# processor_board.net
KiCad netlist of a schematic drawn in EAGLE
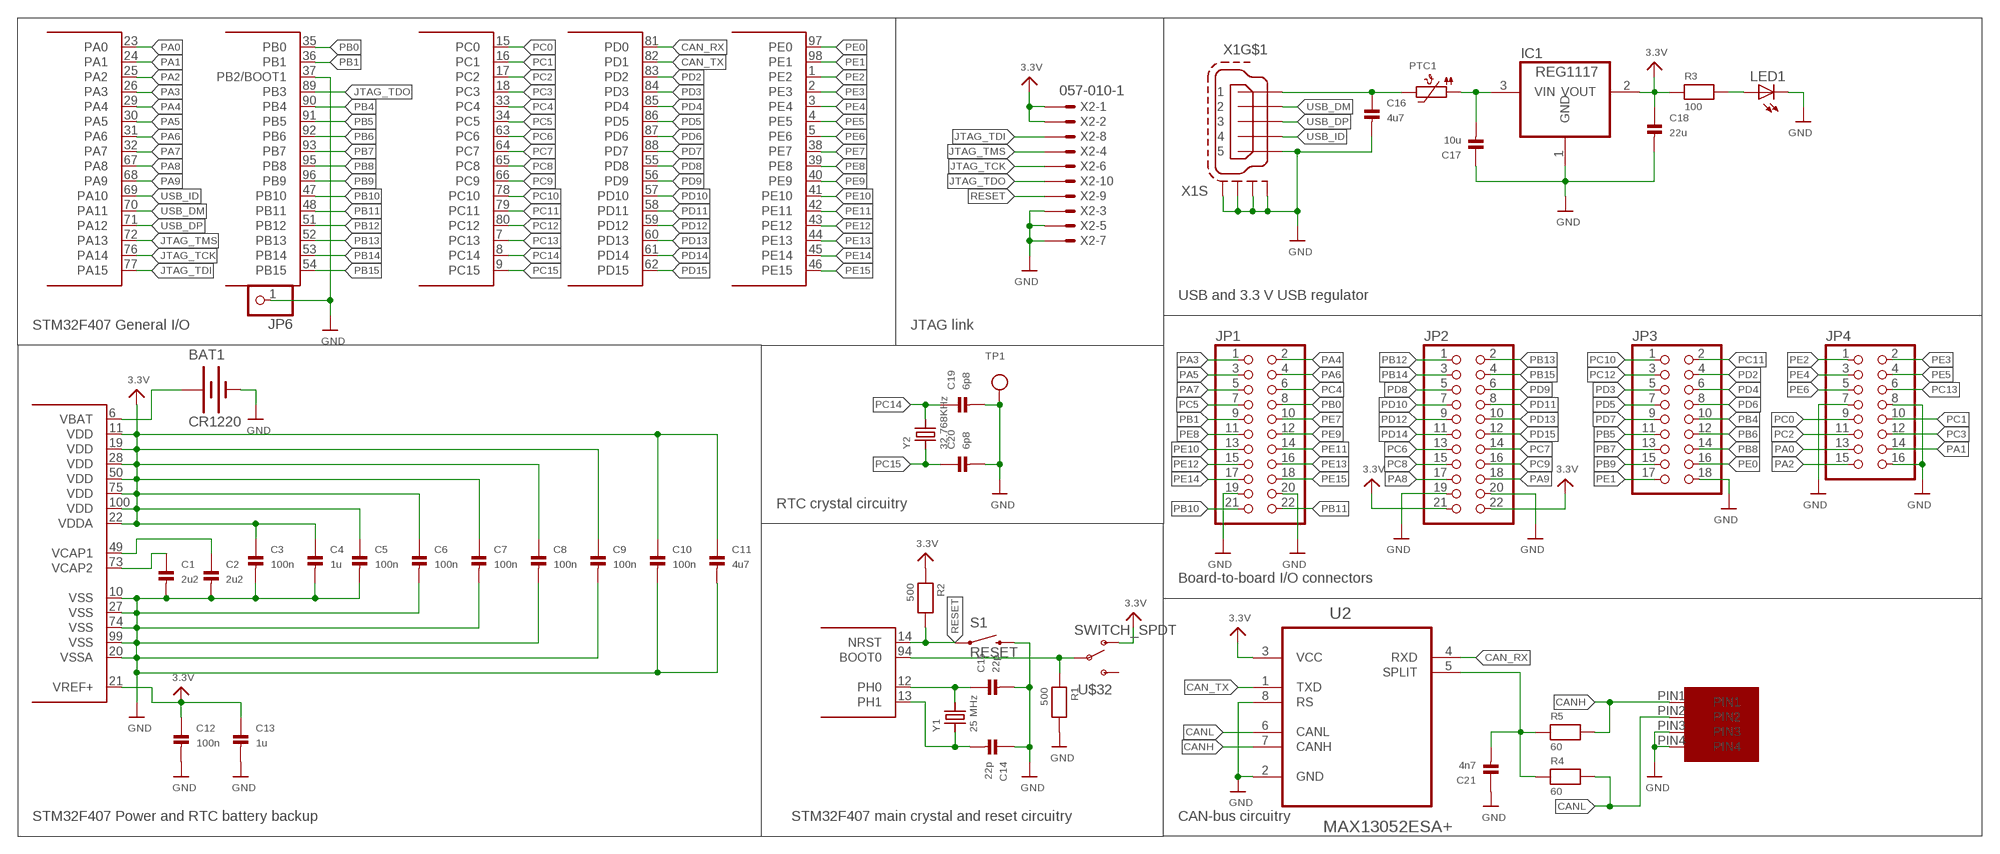
[diagram p0: schematic, sheet 1]

(export (version "E")
  (design (tool "Eeschema 10.0.6"))
  (components
    (comp (ref "BAT1")
      (value "CR1220")
      (footprint "eagle-import:BATTCON_12MM_PTH")
      (libsource (lib "eagle-import") (part "BATTERY12PTH"))
    )
    (comp (ref "C1")
      (value "2u2")
      (footprint "eagle-import:_0603MP")
      (libsource (lib "eagle-import") (part "CAP_CERAMIC_0603MP"))
    )
    (comp (ref "C2")
      (value "2u2")
      (footprint "eagle-import:_0603MP")
      (libsource (lib "eagle-import") (part "CAP_CERAMIC_0603MP"))
    )
    (comp (ref "C3")
      (value "100n")
      (footprint "eagle-import:_0603MP")
      (libsource (lib "eagle-import") (part "CAP_CERAMIC_0603MP"))
    )
    (comp (ref "C4")
      (value "1u")
      (footprint "eagle-import:_0603MP")
      (libsource (lib "eagle-import") (part "CAP_CERAMIC_0603MP"))
    )
    (comp (ref "C5")
      (value "100n")
      (footprint "eagle-import:_0603MP")
      (libsource (lib "eagle-import") (part "CAP_CERAMIC_0603MP"))
    )
    (comp (ref "C6")
      (value "100n")
      (footprint "eagle-import:_0603MP")
      (libsource (lib "eagle-import") (part "CAP_CERAMIC_0603MP"))
    )
    (comp (ref "C7")
      (value "100n")
      (footprint "eagle-import:_0603MP")
      (libsource (lib "eagle-import") (part "CAP_CERAMIC_0603MP"))
    )
    (comp (ref "C8")
      (value "100n")
      (footprint "eagle-import:_0603MP")
      (libsource (lib "eagle-import") (part "CAP_CERAMIC_0603MP"))
    )
    (comp (ref "C9")
      (value "100n")
      (footprint "eagle-import:_0603MP")
      (libsource (lib "eagle-import") (part "CAP_CERAMIC_0603MP"))
    )
    (comp (ref "C10")
      (value "100n")
      (footprint "eagle-import:_0603MP")
      (libsource (lib "eagle-import") (part "CAP_CERAMIC_0603MP"))
    )
    (comp (ref "C11")
      (value "4u7")
      (footprint "eagle-import:_0603MP")
      (libsource (lib "eagle-import") (part "CAP_CERAMIC_0603MP"))
    )
    (comp (ref "C12")
      (value "100n")
      (footprint "eagle-import:_0603MP")
      (libsource (lib "eagle-import") (part "CAP_CERAMIC_0603MP"))
    )
    (comp (ref "C13")
      (value "1u")
      (footprint "eagle-import:_0603MP")
      (libsource (lib "eagle-import") (part "CAP_CERAMIC_0603MP"))
    )
    (comp (ref "C14")
      (value "22p")
      (footprint "eagle-import:_0603MP")
      (libsource (lib "eagle-import") (part "CAP_CERAMIC_0603MP"))
    )
    (comp (ref "C15")
      (value "22p")
      (footprint "eagle-import:_0603MP")
      (libsource (lib "eagle-import") (part "CAP_CERAMIC_0603MP"))
    )
    (comp (ref "C16")
      (value "4u7")
      (footprint "eagle-import:_0603MP")
      (libsource (lib "eagle-import") (part "CAP_CERAMIC_0603MP"))
    )
    (comp (ref "C17")
      (value "10u")
      (footprint "eagle-import:_0603MP")
      (libsource (lib "eagle-import") (part "CAP_CERAMIC_0603MP"))
    )
    (comp (ref "C18")
      (value "22u")
      (footprint "eagle-import:_0603MP")
      (libsource (lib "eagle-import") (part "CAP_CERAMIC_0603MP"))
    )
    (comp (ref "C19")
      (value "6p8")
      (footprint "eagle-import:_0603MP")
      (libsource (lib "eagle-import") (part "CAP_CERAMIC_0603MP"))
    )
    (comp (ref "C20")
      (value "6p8")
      (footprint "eagle-import:_0603MP")
      (libsource (lib "eagle-import") (part "CAP_CERAMIC_0603MP"))
    )
    (comp (ref "C21")
      (value "4n7")
      (footprint "eagle-import:_0603")
      (libsource (lib "eagle-import") (part "CAP_CERAMIC_0603"))
    )
    (comp (ref "IC1")
      (value "REG1117")
      (footprint "eagle-import:SOT223")
      (libsource (lib "eagle-import") (part "REG1117"))
    )
    (comp (ref "JP1")
      (value "PINHD-2X11")
      (footprint "eagle-import:2X11")
      (libsource (lib "eagle-import") (part "PINHD-2X11"))
    )
    (comp (ref "JP2")
      (value "PINHD-2X11")
      (footprint "eagle-import:2X11")
      (libsource (lib "eagle-import") (part "PINHD-2X11"))
    )
    (comp (ref "JP3")
      (value "PINHD-2X9")
      (footprint "eagle-import:2X09")
      (libsource (lib "eagle-import") (part "PINHD-2X9"))
    )
    (comp (ref "JP4")
      (value "PINHD-2X8")
      (footprint "eagle-import:2X08")
      (libsource (lib "eagle-import") (part "PINHD-2X8"))
    )
    (comp (ref "JP6")
      (value "PINHD-1X1")
      (footprint "eagle-import:1X01")
      (libsource (lib "eagle-import") (part "PINHD-1X1"))
    )
    (comp (ref "LED1")
      (value "LEDCHIPLED_1206")
      (footprint "eagle-import:CHIPLED_1206")
      (libsource (lib "eagle-import") (part "LEDCHIPLED_1206"))
    )
    (comp (ref "PTC1")
      (value "PTC1206")
      (footprint "eagle-import:1206")
      (libsource (lib "eagle-import") (part "PTC1206"))
    )
    (comp (ref "R1")
      (value "500")
      (footprint "eagle-import:_0603MP")
      (libsource (lib "eagle-import") (part "RESISTOR_0603MP"))
    )
    (comp (ref "R2")
      (value "500")
      (footprint "eagle-import:_0603MP")
      (libsource (lib "eagle-import") (part "RESISTOR_0603MP"))
    )
    (comp (ref "R3")
      (value "100")
      (footprint "eagle-import:_0603MP")
      (libsource (lib "eagle-import") (part "RESISTOR_0603MP"))
    )
    (comp (ref "R4")
      (value "60")
      (footprint "eagle-import:_0603")
      (libsource (lib "eagle-import") (part "RESISTOR_0603"))
    )
    (comp (ref "R5")
      (value "60")
      (footprint "eagle-import:_0603")
      (libsource (lib "eagle-import") (part "RESISTOR_0603"))
    )
    (comp (ref "S1")
      (value "RESET")
      (footprint "eagle-import:TACTILE-SWITCH-1101NE")
      (libsource (lib "eagle-import") (part "SWITCH-MOMENTARY-2SMD-1101NE"))
    )
    (comp (ref "TP1")
      (value "TESTPOINT0.1\"")
      (footprint "eagle-import:1X01_ROUND")
      (libsource (lib "eagle-import") (part "TESTPOINT0.1{dblquote}"))
    )
    (comp (ref "U$23")
      (value "MICROFIT4")
      (footprint "eagle-import:MICROFIT4SOCK")
      (libsource (lib "eagle-import") (part "MICROFIT4"))
    )
    (comp (ref "U$32")
      (value "SWITCH_SPDT")
      (footprint "eagle-import:KPS-1290")
      (libsource (lib "eagle-import") (part "SWITCH_SPDT"))
    )
    (comp (ref "U1")
      (value "STM32F4-100")
      (footprint "eagle-import:SQFP-S-14X14-100")
      (libsource (lib "eagle-import") (part "STM32F4-100"))
    )
    (comp (ref "U2")
      (value "MAX13052ESA+")
      (footprint "eagle-import:SOIC127P600X175-8N")
      (libsource (lib "eagle-import") (part "MAX13052ESA+"))
    )
    (comp (ref "X1")
      (value "MINI-USB-SCHIELD-32005-201")
      (footprint "eagle-import:32005-201")
      (libsource (lib "eagle-import") (part "MINI-USB-SCHIELD-32005-201"))
    )
    (comp (ref "X2")
      (value "057-010-1")
      (footprint "eagle-import:057-010-1")
      (libsource (lib "eagle-import") (part "057-010-1"))
    )
    (comp (ref "Y1")
      (value "25 MHz")
      (footprint "eagle-import:CRYSTAL_2.5X2")
      (libsource (lib "eagle-import") (part "CRYSTAL2.5X2.0MM"))
    )
    (comp (ref "Y2")
      (value "32.768KHz")
      (footprint "eagle-import:CRYSTAL_CYL_2X6MM_SMT")
      (libsource (lib "eagle-import") (part "CRYSTAL32.768"))
    )
  )
  (nets
    (net (code "1") (name "3.3V") (class "Default")
      (node (ref "C10") (pin "1") (pinfunction "P$1_1") (pintype "passive"))
      (node (ref "C11") (pin "1") (pinfunction "P$1_1") (pintype "passive"))
      (node (ref "C12") (pin "1") (pinfunction "P$1_1") (pintype "passive"))
      (node (ref "C13") (pin "1") (pinfunction "P$1_1") (pintype "passive"))
      (node (ref "C18") (pin "1") (pinfunction "P$1_1") (pintype "passive"))
      (node (ref "C3") (pin "1") (pinfunction "P$1_1") (pintype "passive"))
      (node (ref "C4") (pin "1") (pinfunction "P$1_1") (pintype "passive"))
      (node (ref "C5") (pin "1") (pinfunction "P$1_1") (pintype "passive"))
      (node (ref "C6") (pin "1") (pinfunction "P$1_1") (pintype "passive"))
      (node (ref "C7") (pin "1") (pinfunction "P$1_1") (pintype "passive"))
      (node (ref "C8") (pin "1") (pinfunction "P$1_1") (pintype "passive"))
      (node (ref "C9") (pin "1") (pinfunction "P$1_1") (pintype "passive"))
      (node (ref "IC1") (pin "2") (pinfunction "VOUT_2") (pintype "output"))
      (node (ref "JP2") (pin "21") (pinfunction "21_21") (pintype "passive"))
      (node (ref "JP2") (pin "22") (pinfunction "22_22") (pintype "passive"))
      (node (ref "R2") (pin "1") (pinfunction "1_1") (pintype "passive"))
      (node (ref "R3") (pin "1") (pinfunction "1_1") (pintype "passive"))
      (node (ref "U$32") (pin "O") (pinfunction "O_O") (pintype "passive"))
      (node (ref "U1") (pin "100") (pinfunction "VDD_100") (pintype "power_in"))
      (node (ref "U1") (pin "11") (pinfunction "VDD_11") (pintype "power_in"))
      (node (ref "U1") (pin "19") (pinfunction "VDD_19") (pintype "power_in"))
      (node (ref "U1") (pin "21") (pinfunction "VREF+_21") (pintype "passive"))
      (node (ref "U1") (pin "22") (pinfunction "VDDA_22") (pintype "power_in"))
      (node (ref "U1") (pin "28") (pinfunction "VDD_28") (pintype "power_in"))
      (node (ref "U1") (pin "50") (pinfunction "VDD_50") (pintype "power_in"))
      (node (ref "U1") (pin "75") (pinfunction "VDD_75") (pintype "power_in"))
      (node (ref "U2") (pin "3") (pinfunction "VCC_3") (pintype "power_in"))
      (node (ref "X2") (pin "1") (pinfunction "S_1") (pintype "passive"))
      (node (ref "X2") (pin "2") (pinfunction "S_2") (pintype "passive"))
    )
    (net (code "2") (name "CANH") (class "Default")
      (node (ref "R5") (pin "2") (pinfunction "2_2") (pintype "passive"))
      (node (ref "U$23") (pin "PIN1") (pinfunction "PIN1_PIN1") (pintype "bidirectional"))
      (node (ref "U2") (pin "7") (pinfunction "CANH_7") (pintype "input"))
    )
    (net (code "3") (name "CANL") (class "Default")
      (node (ref "R4") (pin "2") (pinfunction "2_2") (pintype "passive"))
      (node (ref "U$23") (pin "PIN2") (pinfunction "PIN2_PIN2") (pintype "bidirectional"))
      (node (ref "U2") (pin "6") (pinfunction "CANL_6") (pintype "input"))
    )
    (net (code "4") (name "CAN_RX") (class "Default")
      (node (ref "U1") (pin "81") (pinfunction "PD0_81") (pintype "bidirectional"))
      (node (ref "U2") (pin "4") (pinfunction "RXD_4") (pintype "output"))
    )
    (net (code "5") (name "CAN_TX") (class "Default")
      (node (ref "U1") (pin "82") (pinfunction "PD1_82") (pintype "bidirectional"))
      (node (ref "U2") (pin "1") (pinfunction "TXD_1") (pintype "input"))
    )
    (net (code "6") (name "GND") (class "Default")
      (node (ref "BAT1") (pin "GND") (pinfunction "-_GND") (pintype "power_in"))
      (node (ref "C1") (pin "2") (pinfunction "P$2_2") (pintype "passive"))
      (node (ref "C10") (pin "2") (pinfunction "P$2_2") (pintype "passive"))
      (node (ref "C11") (pin "2") (pinfunction "P$2_2") (pintype "passive"))
      (node (ref "C12") (pin "2") (pinfunction "P$2_2") (pintype "passive"))
      (node (ref "C13") (pin "2") (pinfunction "P$2_2") (pintype "passive"))
      (node (ref "C14") (pin "1") (pinfunction "P$1_1") (pintype "passive"))
      (node (ref "C15") (pin "2") (pinfunction "P$2_2") (pintype "passive"))
      (node (ref "C16") (pin "2") (pinfunction "P$2_2") (pintype "passive"))
      (node (ref "C17") (pin "1") (pinfunction "P$1_1") (pintype "passive"))
      (node (ref "C18") (pin "2") (pinfunction "P$2_2") (pintype "passive"))
      (node (ref "C19") (pin "2") (pinfunction "P$2_2") (pintype "passive"))
      (node (ref "C2") (pin "2") (pinfunction "P$2_2") (pintype "passive"))
      (node (ref "C20") (pin "2") (pinfunction "P$2_2") (pintype "passive"))
      (node (ref "C21") (pin "1") (pinfunction "P$1_1") (pintype "passive"))
      (node (ref "C3") (pin "2") (pinfunction "P$2_2") (pintype "passive"))
      (node (ref "C4") (pin "2") (pinfunction "P$2_2") (pintype "passive"))
      (node (ref "C5") (pin "2") (pinfunction "P$2_2") (pintype "passive"))
      (node (ref "C6") (pin "2") (pinfunction "P$2_2") (pintype "passive"))
      (node (ref "C7") (pin "2") (pinfunction "P$2_2") (pintype "passive"))
      (node (ref "C8") (pin "2") (pinfunction "P$2_2") (pintype "passive"))
      (node (ref "C9") (pin "2") (pinfunction "P$2_2") (pintype "passive"))
      (node (ref "IC1") (pin "1") (pinfunction "GND_1") (pintype "power_in"))
      (node (ref "JP1") (pin "19") (pinfunction "19_19") (pintype "passive"))
      (node (ref "JP1") (pin "20") (pinfunction "20_20") (pintype "passive"))
      (node (ref "JP2") (pin "19") (pinfunction "19_19") (pintype "passive"))
      (node (ref "JP2") (pin "20") (pinfunction "20_20") (pintype "passive"))
      (node (ref "JP3") (pin "18") (pinfunction "18_18") (pintype "passive"))
      (node (ref "JP4") (pin "16") (pinfunction "16_16") (pintype "passive"))
      (node (ref "JP4") (pin "7") (pinfunction "7_7") (pintype "passive"))
      (node (ref "JP4") (pin "8") (pinfunction "8_8") (pintype "passive"))
      (node (ref "JP6") (pin "1") (pinfunction "1_1") (pintype "passive"))
      (node (ref "LED1") (pin "C") (pinfunction "C_C") (pintype "passive"))
      (node (ref "R1") (pin "2") (pinfunction "2_2") (pintype "passive"))
      (node (ref "S1") (pin "2") (pinfunction "2_2") (pintype "passive"))
      (node (ref "TP1") (pin "1") (pinfunction "P$1_1") (pintype "bidirectional"))
      (node (ref "U$23") (pin "PIN3") (pinfunction "PIN3_PIN3") (pintype "bidirectional"))
      (node (ref "U$23") (pin "PIN4") (pinfunction "PIN4_PIN4") (pintype "bidirectional"))
      (node (ref "U1") (pin "10") (pinfunction "VSS_10") (pintype "power_in"))
      (node (ref "U1") (pin "20") (pinfunction "VSSA_20") (pintype "power_in"))
      (node (ref "U1") (pin "27") (pinfunction "VSS_27") (pintype "power_in"))
      (node (ref "U1") (pin "37") (pinfunction "PB2/BOOT1_37") (pintype "bidirectional"))
      (node (ref "U1") (pin "74") (pinfunction "VSS_74") (pintype "power_in"))
      (node (ref "U1") (pin "99") (pinfunction "VSS_99") (pintype "power_in"))
      (node (ref "U2") (pin "2") (pinfunction "GND_2") (pintype "passive"))
      (node (ref "U2") (pin "8") (pinfunction "RS_8") (pintype "input"))
      (node (ref "X1") (pin "5") (pinfunction "5_5") (pintype "passive"))
      (node (ref "X1") (pin "M1") (pinfunction "S1_M1") (pintype "passive"))
      (node (ref "X1") (pin "M2") (pinfunction "S2_M2") (pintype "passive"))
      (node (ref "X1") (pin "M3") (pinfunction "S3_M3") (pintype "passive"))
      (node (ref "X1") (pin "M4") (pinfunction "S4_M4") (pintype "passive"))
      (node (ref "X2") (pin "3") (pinfunction "S_3") (pintype "passive"))
      (node (ref "X2") (pin "5") (pinfunction "S_5") (pintype "passive"))
      (node (ref "X2") (pin "7") (pinfunction "S_7") (pintype "passive"))
    )
    (net (code "7") (name "JTAG_TCK") (class "Default")
      (node (ref "U1") (pin "76") (pinfunction "PA14_76") (pintype "bidirectional"))
      (node (ref "X2") (pin "6") (pinfunction "S_6") (pintype "passive"))
    )
    (net (code "8") (name "JTAG_TDI") (class "Default")
      (node (ref "U1") (pin "77") (pinfunction "PA15_77") (pintype "bidirectional"))
      (node (ref "X2") (pin "8") (pinfunction "S_8") (pintype "passive"))
    )
    (net (code "9") (name "JTAG_TDO") (class "Default")
      (node (ref "U1") (pin "89") (pinfunction "PB3_89") (pintype "bidirectional"))
      (node (ref "X2") (pin "10") (pinfunction "S_10") (pintype "passive"))
    )
    (net (code "10") (name "JTAG_TMS") (class "Default")
      (node (ref "U1") (pin "72") (pinfunction "PA13_72") (pintype "bidirectional"))
      (node (ref "X2") (pin "4") (pinfunction "S_4") (pintype "passive"))
    )
    (net (code "11") (name "Net-(BAT1-+)") (class "Default")
      (node (ref "BAT1") (pin "VCC@1") (pinfunction "+_VCC@1") (pintype "power_in"))
      (node (ref "U1") (pin "6") (pinfunction "VBAT_6") (pintype "power_in"))
    )
    (net (code "12") (name "Net-(C1-P$1)") (class "Default")
      (node (ref "C1") (pin "1") (pinfunction "P$1_1") (pintype "passive"))
      (node (ref "U1") (pin "73") (pinfunction "VCAP2_73") (pintype "passive"))
    )
    (net (code "13") (name "Net-(C2-P$1)") (class "Default")
      (node (ref "C2") (pin "1") (pinfunction "P$1_1") (pintype "passive"))
      (node (ref "U1") (pin "49") (pinfunction "VCAP1_49") (pintype "passive"))
    )
    (net (code "14") (name "Net-(C14-P$2)") (class "Default")
      (node (ref "C14") (pin "2") (pinfunction "P$2_2") (pintype "passive"))
      (node (ref "U1") (pin "13") (pinfunction "PH1_13") (pintype "bidirectional"))
      (node (ref "Y1") (pin "1") (pinfunction "1_1") (pintype "passive"))
    )
    (net (code "15") (name "Net-(C15-P$1)") (class "Default")
      (node (ref "C15") (pin "1") (pinfunction "P$1_1") (pintype "passive"))
      (node (ref "U1") (pin "12") (pinfunction "PH0_12") (pintype "bidirectional"))
      (node (ref "Y1") (pin "3") (pinfunction "2_3") (pintype "passive"))
    )
    (net (code "16") (name "Net-(C16-P$1)") (class "Default")
      (node (ref "C16") (pin "1") (pinfunction "P$1_1") (pintype "passive"))
      (node (ref "PTC1") (pin "2") (pinfunction "2_2") (pintype "passive"))
      (node (ref "X1") (pin "1") (pinfunction "1_1") (pintype "passive"))
    )
    (net (code "17") (name "Net-(C17-P$2)") (class "Default")
      (node (ref "C17") (pin "2") (pinfunction "P$2_2") (pintype "passive"))
      (node (ref "IC1") (pin "3") (pinfunction "VIN_3") (pintype "input"))
      (node (ref "PTC1") (pin "1") (pinfunction "1_1") (pintype "passive"))
    )
    (net (code "18") (name "Net-(C21-P$2)") (class "Default")
      (node (ref "C21") (pin "2") (pinfunction "P$2_2") (pintype "passive"))
      (node (ref "R4") (pin "1") (pinfunction "1_1") (pintype "passive"))
      (node (ref "R5") (pin "1") (pinfunction "1_1") (pintype "passive"))
      (node (ref "U2") (pin "5") (pinfunction "SPLIT_5") (pintype "output"))
    )
    (net (code "19") (name "Net-(LED1-PadA)") (class "Default")
      (node (ref "LED1") (pin "A") (pinfunction "A_A") (pintype "passive"))
      (node (ref "R3") (pin "2") (pinfunction "2_2") (pintype "passive"))
    )
    (net (code "20") (name "Net-(U1G-BOOT0)") (class "Default")
      (node (ref "R1") (pin "1") (pinfunction "1_1") (pintype "passive"))
      (node (ref "U$32") (pin "P") (pinfunction "P_P") (pintype "passive"))
      (node (ref "U1") (pin "94") (pinfunction "BOOT0_94") (pintype "bidirectional"))
    )
    (net (code "21") (name "PA0") (class "Default")
      (node (ref "JP4") (pin "13") (pinfunction "13_13") (pintype "passive"))
      (node (ref "U1") (pin "23") (pinfunction "PA0_23") (pintype "bidirectional"))
    )
    (net (code "22") (name "PA1") (class "Default")
      (node (ref "JP4") (pin "14") (pinfunction "14_14") (pintype "passive"))
      (node (ref "U1") (pin "24") (pinfunction "PA1_24") (pintype "bidirectional"))
    )
    (net (code "23") (name "PA2") (class "Default")
      (node (ref "JP4") (pin "15") (pinfunction "15_15") (pintype "passive"))
      (node (ref "U1") (pin "25") (pinfunction "PA2_25") (pintype "bidirectional"))
    )
    (net (code "24") (name "PA3") (class "Default")
      (node (ref "JP1") (pin "1") (pinfunction "1_1") (pintype "passive"))
      (node (ref "U1") (pin "26") (pinfunction "PA3_26") (pintype "bidirectional"))
    )
    (net (code "25") (name "PA4") (class "Default")
      (node (ref "JP1") (pin "2") (pinfunction "2_2") (pintype "passive"))
      (node (ref "U1") (pin "29") (pinfunction "PA4_29") (pintype "bidirectional"))
    )
    (net (code "26") (name "PA5") (class "Default")
      (node (ref "JP1") (pin "3") (pinfunction "3_3") (pintype "passive"))
      (node (ref "U1") (pin "30") (pinfunction "PA5_30") (pintype "bidirectional"))
    )
    (net (code "27") (name "PA6") (class "Default")
      (node (ref "JP1") (pin "4") (pinfunction "4_4") (pintype "passive"))
      (node (ref "U1") (pin "31") (pinfunction "PA6_31") (pintype "bidirectional"))
    )
    (net (code "28") (name "PA7") (class "Default")
      (node (ref "JP1") (pin "5") (pinfunction "5_5") (pintype "passive"))
      (node (ref "U1") (pin "32") (pinfunction "PA7_32") (pintype "bidirectional"))
    )
    (net (code "29") (name "PA8") (class "Default")
      (node (ref "JP2") (pin "17") (pinfunction "17_17") (pintype "passive"))
      (node (ref "U1") (pin "67") (pinfunction "PA8_67") (pintype "bidirectional"))
    )
    (net (code "30") (name "PA9") (class "Default")
      (node (ref "JP2") (pin "18") (pinfunction "18_18") (pintype "passive"))
      (node (ref "U1") (pin "68") (pinfunction "PA9_68") (pintype "bidirectional"))
    )
    (net (code "31") (name "PB0") (class "Default")
      (node (ref "JP1") (pin "8") (pinfunction "8_8") (pintype "passive"))
      (node (ref "U1") (pin "35") (pinfunction "PB0_35") (pintype "bidirectional"))
    )
    (net (code "32") (name "PB1") (class "Default")
      (node (ref "JP1") (pin "9") (pinfunction "9_9") (pintype "passive"))
      (node (ref "U1") (pin "36") (pinfunction "PB1_36") (pintype "bidirectional"))
    )
    (net (code "33") (name "PB4") (class "Default")
      (node (ref "JP3") (pin "10") (pinfunction "10_10") (pintype "passive"))
      (node (ref "U1") (pin "90") (pinfunction "PB4_90") (pintype "bidirectional"))
    )
    (net (code "34") (name "PB5") (class "Default")
      (node (ref "JP3") (pin "11") (pinfunction "11_11") (pintype "passive"))
      (node (ref "U1") (pin "91") (pinfunction "PB5_91") (pintype "bidirectional"))
    )
    (net (code "35") (name "PB6") (class "Default")
      (node (ref "JP3") (pin "12") (pinfunction "12_12") (pintype "passive"))
      (node (ref "U1") (pin "92") (pinfunction "PB6_92") (pintype "bidirectional"))
    )
    (net (code "36") (name "PB7") (class "Default")
      (node (ref "JP3") (pin "13") (pinfunction "13_13") (pintype "passive"))
      (node (ref "U1") (pin "93") (pinfunction "PB7_93") (pintype "bidirectional"))
    )
    (net (code "37") (name "PB8") (class "Default")
      (node (ref "JP3") (pin "14") (pinfunction "14_14") (pintype "passive"))
      (node (ref "U1") (pin "95") (pinfunction "PB8_95") (pintype "bidirectional"))
    )
    (net (code "38") (name "PB9") (class "Default")
      (node (ref "JP3") (pin "15") (pinfunction "15_15") (pintype "passive"))
      (node (ref "U1") (pin "96") (pinfunction "PB9_96") (pintype "bidirectional"))
    )
    (net (code "39") (name "PB10") (class "Default")
      (node (ref "JP1") (pin "21") (pinfunction "21_21") (pintype "passive"))
      (node (ref "U1") (pin "47") (pinfunction "PB10_47") (pintype "bidirectional"))
    )
    (net (code "40") (name "PB11") (class "Default")
      (node (ref "JP1") (pin "22") (pinfunction "22_22") (pintype "passive"))
      (node (ref "U1") (pin "48") (pinfunction "PB11_48") (pintype "bidirectional"))
    )
    (net (code "41") (name "PB12") (class "Default")
      (node (ref "JP2") (pin "1") (pinfunction "1_1") (pintype "passive"))
      (node (ref "U1") (pin "51") (pinfunction "PB12_51") (pintype "bidirectional"))
    )
    (net (code "42") (name "PB13") (class "Default")
      (node (ref "JP2") (pin "2") (pinfunction "2_2") (pintype "passive"))
      (node (ref "U1") (pin "52") (pinfunction "PB13_52") (pintype "bidirectional"))
    )
    (net (code "43") (name "PB14") (class "Default")
      (node (ref "JP2") (pin "3") (pinfunction "3_3") (pintype "passive"))
      (node (ref "U1") (pin "53") (pinfunction "PB14_53") (pintype "bidirectional"))
    )
    (net (code "44") (name "PB15") (class "Default")
      (node (ref "JP2") (pin "4") (pinfunction "4_4") (pintype "passive"))
      (node (ref "U1") (pin "54") (pinfunction "PB15_54") (pintype "bidirectional"))
    )
    (net (code "45") (name "PC0") (class "Default")
      (node (ref "JP4") (pin "9") (pinfunction "9_9") (pintype "passive"))
      (node (ref "U1") (pin "15") (pinfunction "PC0_15") (pintype "bidirectional"))
    )
    (net (code "46") (name "PC1") (class "Default")
      (node (ref "JP4") (pin "10") (pinfunction "10_10") (pintype "passive"))
      (node (ref "U1") (pin "16") (pinfunction "PC1_16") (pintype "bidirectional"))
    )
    (net (code "47") (name "PC2") (class "Default")
      (node (ref "JP4") (pin "11") (pinfunction "11_11") (pintype "passive"))
      (node (ref "U1") (pin "17") (pinfunction "PC2_17") (pintype "bidirectional"))
    )
    (net (code "48") (name "PC3") (class "Default")
      (node (ref "JP4") (pin "12") (pinfunction "12_12") (pintype "passive"))
      (node (ref "U1") (pin "18") (pinfunction "PC3_18") (pintype "bidirectional"))
    )
    (net (code "49") (name "PC4") (class "Default")
      (node (ref "JP1") (pin "6") (pinfunction "6_6") (pintype "passive"))
      (node (ref "U1") (pin "33") (pinfunction "PC4_33") (pintype "bidirectional"))
    )
    (net (code "50") (name "PC5") (class "Default")
      (node (ref "JP1") (pin "7") (pinfunction "7_7") (pintype "passive"))
      (node (ref "U1") (pin "34") (pinfunction "PC5_34") (pintype "bidirectional"))
    )
    (net (code "51") (name "PC6") (class "Default")
      (node (ref "JP2") (pin "13") (pinfunction "13_13") (pintype "passive"))
      (node (ref "U1") (pin "63") (pinfunction "PC6_63") (pintype "bidirectional"))
    )
    (net (code "52") (name "PC7") (class "Default")
      (node (ref "JP2") (pin "14") (pinfunction "14_14") (pintype "passive"))
      (node (ref "U1") (pin "64") (pinfunction "PC7_64") (pintype "bidirectional"))
    )
    (net (code "53") (name "PC8") (class "Default")
      (node (ref "JP2") (pin "15") (pinfunction "15_15") (pintype "passive"))
      (node (ref "U1") (pin "65") (pinfunction "PC8_65") (pintype "bidirectional"))
    )
    (net (code "54") (name "PC9") (class "Default")
      (node (ref "JP2") (pin "16") (pinfunction "16_16") (pintype "passive"))
      (node (ref "U1") (pin "66") (pinfunction "PC9_66") (pintype "bidirectional"))
    )
    (net (code "55") (name "PC10") (class "Default")
      (node (ref "JP3") (pin "1") (pinfunction "1_1") (pintype "passive"))
      (node (ref "U1") (pin "78") (pinfunction "PC10_78") (pintype "bidirectional"))
    )
    (net (code "56") (name "PC11") (class "Default")
      (node (ref "JP3") (pin "2") (pinfunction "2_2") (pintype "passive"))
      (node (ref "U1") (pin "79") (pinfunction "PC11_79") (pintype "bidirectional"))
    )
    (net (code "57") (name "PC12") (class "Default")
      (node (ref "JP3") (pin "3") (pinfunction "3_3") (pintype "passive"))
      (node (ref "U1") (pin "80") (pinfunction "PC12_80") (pintype "bidirectional"))
    )
    (net (code "58") (name "PC13") (class "Default")
      (node (ref "JP4") (pin "6") (pinfunction "6_6") (pintype "passive"))
      (node (ref "U1") (pin "7") (pinfunction "PC13_7") (pintype "bidirectional"))
    )
    (net (code "59") (name "PC14") (class "Default")
      (node (ref "C19") (pin "1") (pinfunction "P$1_1") (pintype "passive"))
      (node (ref "U1") (pin "8") (pinfunction "PC14_8") (pintype "bidirectional"))
      (node (ref "Y2") (pin "2") (pinfunction "2_2") (pintype "passive"))
    )
    (net (code "60") (name "PC15") (class "Default")
      (node (ref "C20") (pin "1") (pinfunction "P$1_1") (pintype "passive"))
      (node (ref "U1") (pin "9") (pinfunction "PC15_9") (pintype "bidirectional"))
      (node (ref "Y2") (pin "1") (pinfunction "1_1") (pintype "passive"))
    )
    (net (code "61") (name "PD2") (class "Default")
      (node (ref "JP3") (pin "4") (pinfunction "4_4") (pintype "passive"))
      (node (ref "U1") (pin "83") (pinfunction "PD2_83") (pintype "bidirectional"))
    )
    (net (code "62") (name "PD3") (class "Default")
      (node (ref "JP3") (pin "5") (pinfunction "5_5") (pintype "passive"))
      (node (ref "U1") (pin "84") (pinfunction "PD3_84") (pintype "bidirectional"))
    )
    (net (code "63") (name "PD4") (class "Default")
      (node (ref "JP3") (pin "6") (pinfunction "6_6") (pintype "passive"))
      (node (ref "U1") (pin "85") (pinfunction "PD4_85") (pintype "bidirectional"))
    )
    (net (code "64") (name "PD5") (class "Default")
      (node (ref "JP3") (pin "7") (pinfunction "7_7") (pintype "passive"))
      (node (ref "U1") (pin "86") (pinfunction "PD5_86") (pintype "bidirectional"))
    )
    (net (code "65") (name "PD6") (class "Default")
      (node (ref "JP3") (pin "8") (pinfunction "8_8") (pintype "passive"))
      (node (ref "U1") (pin "87") (pinfunction "PD6_87") (pintype "bidirectional"))
    )
    (net (code "66") (name "PD7") (class "Default")
      (node (ref "JP3") (pin "9") (pinfunction "9_9") (pintype "passive"))
      (node (ref "U1") (pin "88") (pinfunction "PD7_88") (pintype "bidirectional"))
    )
    (net (code "67") (name "PD8") (class "Default")
      (node (ref "JP2") (pin "5") (pinfunction "5_5") (pintype "passive"))
      (node (ref "U1") (pin "55") (pinfunction "PD8_55") (pintype "bidirectional"))
    )
    (net (code "68") (name "PD9") (class "Default")
      (node (ref "JP2") (pin "6") (pinfunction "6_6") (pintype "passive"))
      (node (ref "U1") (pin "56") (pinfunction "PD9_56") (pintype "bidirectional"))
    )
    (net (code "69") (name "PD10") (class "Default")
      (node (ref "JP2") (pin "7") (pinfunction "7_7") (pintype "passive"))
      (node (ref "U1") (pin "57") (pinfunction "PD10_57") (pintype "bidirectional"))
    )
    (net (code "70") (name "PD11") (class "Default")
      (node (ref "JP2") (pin "8") (pinfunction "8_8") (pintype "passive"))
      (node (ref "U1") (pin "58") (pinfunction "PD11_58") (pintype "bidirectional"))
    )
    (net (code "71") (name "PD12") (class "Default")
      (node (ref "JP2") (pin "9") (pinfunction "9_9") (pintype "passive"))
      (node (ref "U1") (pin "59") (pinfunction "PD12_59") (pintype "bidirectional"))
    )
    (net (code "72") (name "PD13") (class "Default")
      (node (ref "JP2") (pin "10") (pinfunction "10_10") (pintype "passive"))
      (node (ref "U1") (pin "60") (pinfunction "PD13_60") (pintype "bidirectional"))
    )
    (net (code "73") (name "PD14") (class "Default")
      (node (ref "JP2") (pin "11") (pinfunction "11_11") (pintype "passive"))
      (node (ref "U1") (pin "61") (pinfunction "PD14_61") (pintype "bidirectional"))
    )
    (net (code "74") (name "PD15") (class "Default")
      (node (ref "JP2") (pin "12") (pinfunction "12_12") (pintype "passive"))
      (node (ref "U1") (pin "62") (pinfunction "PD15_62") (pintype "bidirectional"))
    )
    (net (code "75") (name "PE0") (class "Default")
      (node (ref "JP3") (pin "16") (pinfunction "16_16") (pintype "passive"))
      (node (ref "U1") (pin "97") (pinfunction "PE0_97") (pintype "bidirectional"))
    )
    (net (code "76") (name "PE1") (class "Default")
      (node (ref "JP3") (pin "17") (pinfunction "17_17") (pintype "passive"))
      (node (ref "U1") (pin "98") (pinfunction "PE1_98") (pintype "bidirectional"))
    )
    (net (code "77") (name "PE2") (class "Default")
      (node (ref "JP4") (pin "1") (pinfunction "1_1") (pintype "passive"))
      (node (ref "U1") (pin "1") (pinfunction "PE2_1") (pintype "bidirectional"))
    )
    (net (code "78") (name "PE3") (class "Default")
      (node (ref "JP4") (pin "2") (pinfunction "2_2") (pintype "passive"))
      (node (ref "U1") (pin "2") (pinfunction "PE3_2") (pintype "bidirectional"))
    )
    (net (code "79") (name "PE4") (class "Default")
      (node (ref "JP4") (pin "3") (pinfunction "3_3") (pintype "passive"))
      (node (ref "U1") (pin "3") (pinfunction "PE4_3") (pintype "bidirectional"))
    )
    (net (code "80") (name "PE5") (class "Default")
      (node (ref "JP4") (pin "4") (pinfunction "4_4") (pintype "passive"))
      (node (ref "U1") (pin "4") (pinfunction "PE5_4") (pintype "bidirectional"))
    )
    (net (code "81") (name "PE6") (class "Default")
      (node (ref "JP4") (pin "5") (pinfunction "5_5") (pintype "passive"))
      (node (ref "U1") (pin "5") (pinfunction "PE6_5") (pintype "bidirectional"))
    )
    (net (code "82") (name "PE7") (class "Default")
      (node (ref "JP1") (pin "10") (pinfunction "10_10") (pintype "passive"))
      (node (ref "U1") (pin "38") (pinfunction "PE7_38") (pintype "bidirectional"))
    )
    (net (code "83") (name "PE8") (class "Default")
      (node (ref "JP1") (pin "11") (pinfunction "11_11") (pintype "passive"))
      (node (ref "U1") (pin "39") (pinfunction "PE8_39") (pintype "bidirectional"))
    )
    (net (code "84") (name "PE9") (class "Default")
      (node (ref "JP1") (pin "12") (pinfunction "12_12") (pintype "passive"))
      (node (ref "U1") (pin "40") (pinfunction "PE9_40") (pintype "bidirectional"))
    )
    (net (code "85") (name "PE10") (class "Default")
      (node (ref "JP1") (pin "13") (pinfunction "13_13") (pintype "passive"))
      (node (ref "U1") (pin "41") (pinfunction "PE10_41") (pintype "bidirectional"))
    )
    (net (code "86") (name "PE11") (class "Default")
      (node (ref "JP1") (pin "14") (pinfunction "14_14") (pintype "passive"))
      (node (ref "U1") (pin "42") (pinfunction "PE11_42") (pintype "bidirectional"))
    )
    (net (code "87") (name "PE12") (class "Default")
      (node (ref "JP1") (pin "15") (pinfunction "15_15") (pintype "passive"))
      (node (ref "U1") (pin "43") (pinfunction "PE12_43") (pintype "bidirectional"))
    )
    (net (code "88") (name "PE13") (class "Default")
      (node (ref "JP1") (pin "16") (pinfunction "16_16") (pintype "passive"))
      (node (ref "U1") (pin "44") (pinfunction "PE13_44") (pintype "bidirectional"))
    )
    (net (code "89") (name "PE14") (class "Default")
      (node (ref "JP1") (pin "17") (pinfunction "17_17") (pintype "passive"))
      (node (ref "U1") (pin "45") (pinfunction "PE14_45") (pintype "bidirectional"))
    )
    (net (code "90") (name "PE15") (class "Default")
      (node (ref "JP1") (pin "18") (pinfunction "18_18") (pintype "passive"))
      (node (ref "U1") (pin "46") (pinfunction "PE15_46") (pintype "bidirectional"))
    )
    (net (code "91") (name "RESET") (class "Default")
      (node (ref "R2") (pin "2") (pinfunction "2_2") (pintype "passive"))
      (node (ref "S1") (pin "1") (pinfunction "1_1") (pintype "passive"))
      (node (ref "U1") (pin "14") (pinfunction "NRST_14") (pintype "bidirectional"))
      (node (ref "X2") (pin "9") (pinfunction "S_9") (pintype "passive"))
    )
    (net (code "92") (name "USB_DM") (class "Default")
      (node (ref "U1") (pin "70") (pinfunction "PA11_70") (pintype "bidirectional"))
      (node (ref "X1") (pin "2") (pinfunction "2_2") (pintype "passive"))
    )
    (net (code "93") (name "USB_DP") (class "Default")
      (node (ref "U1") (pin "71") (pinfunction "PA12_71") (pintype "bidirectional"))
      (node (ref "X1") (pin "3") (pinfunction "3_3") (pintype "passive"))
    )
    (net (code "94") (name "USB_ID") (class "Default")
      (node (ref "U1") (pin "69") (pinfunction "PA10_69") (pintype "bidirectional"))
      (node (ref "X1") (pin "4") (pinfunction "4_4") (pintype "passive"))
    )
    (net (code "95") (name "unconnected-(U$32-PadS)") (class "Default")
      (node (ref "U$32") (pin "S") (pinfunction "S_S") (pintype "passive"))
    )
  )
)
